# all.net
KiCad netlist of a schematic drawn in Altium Designer
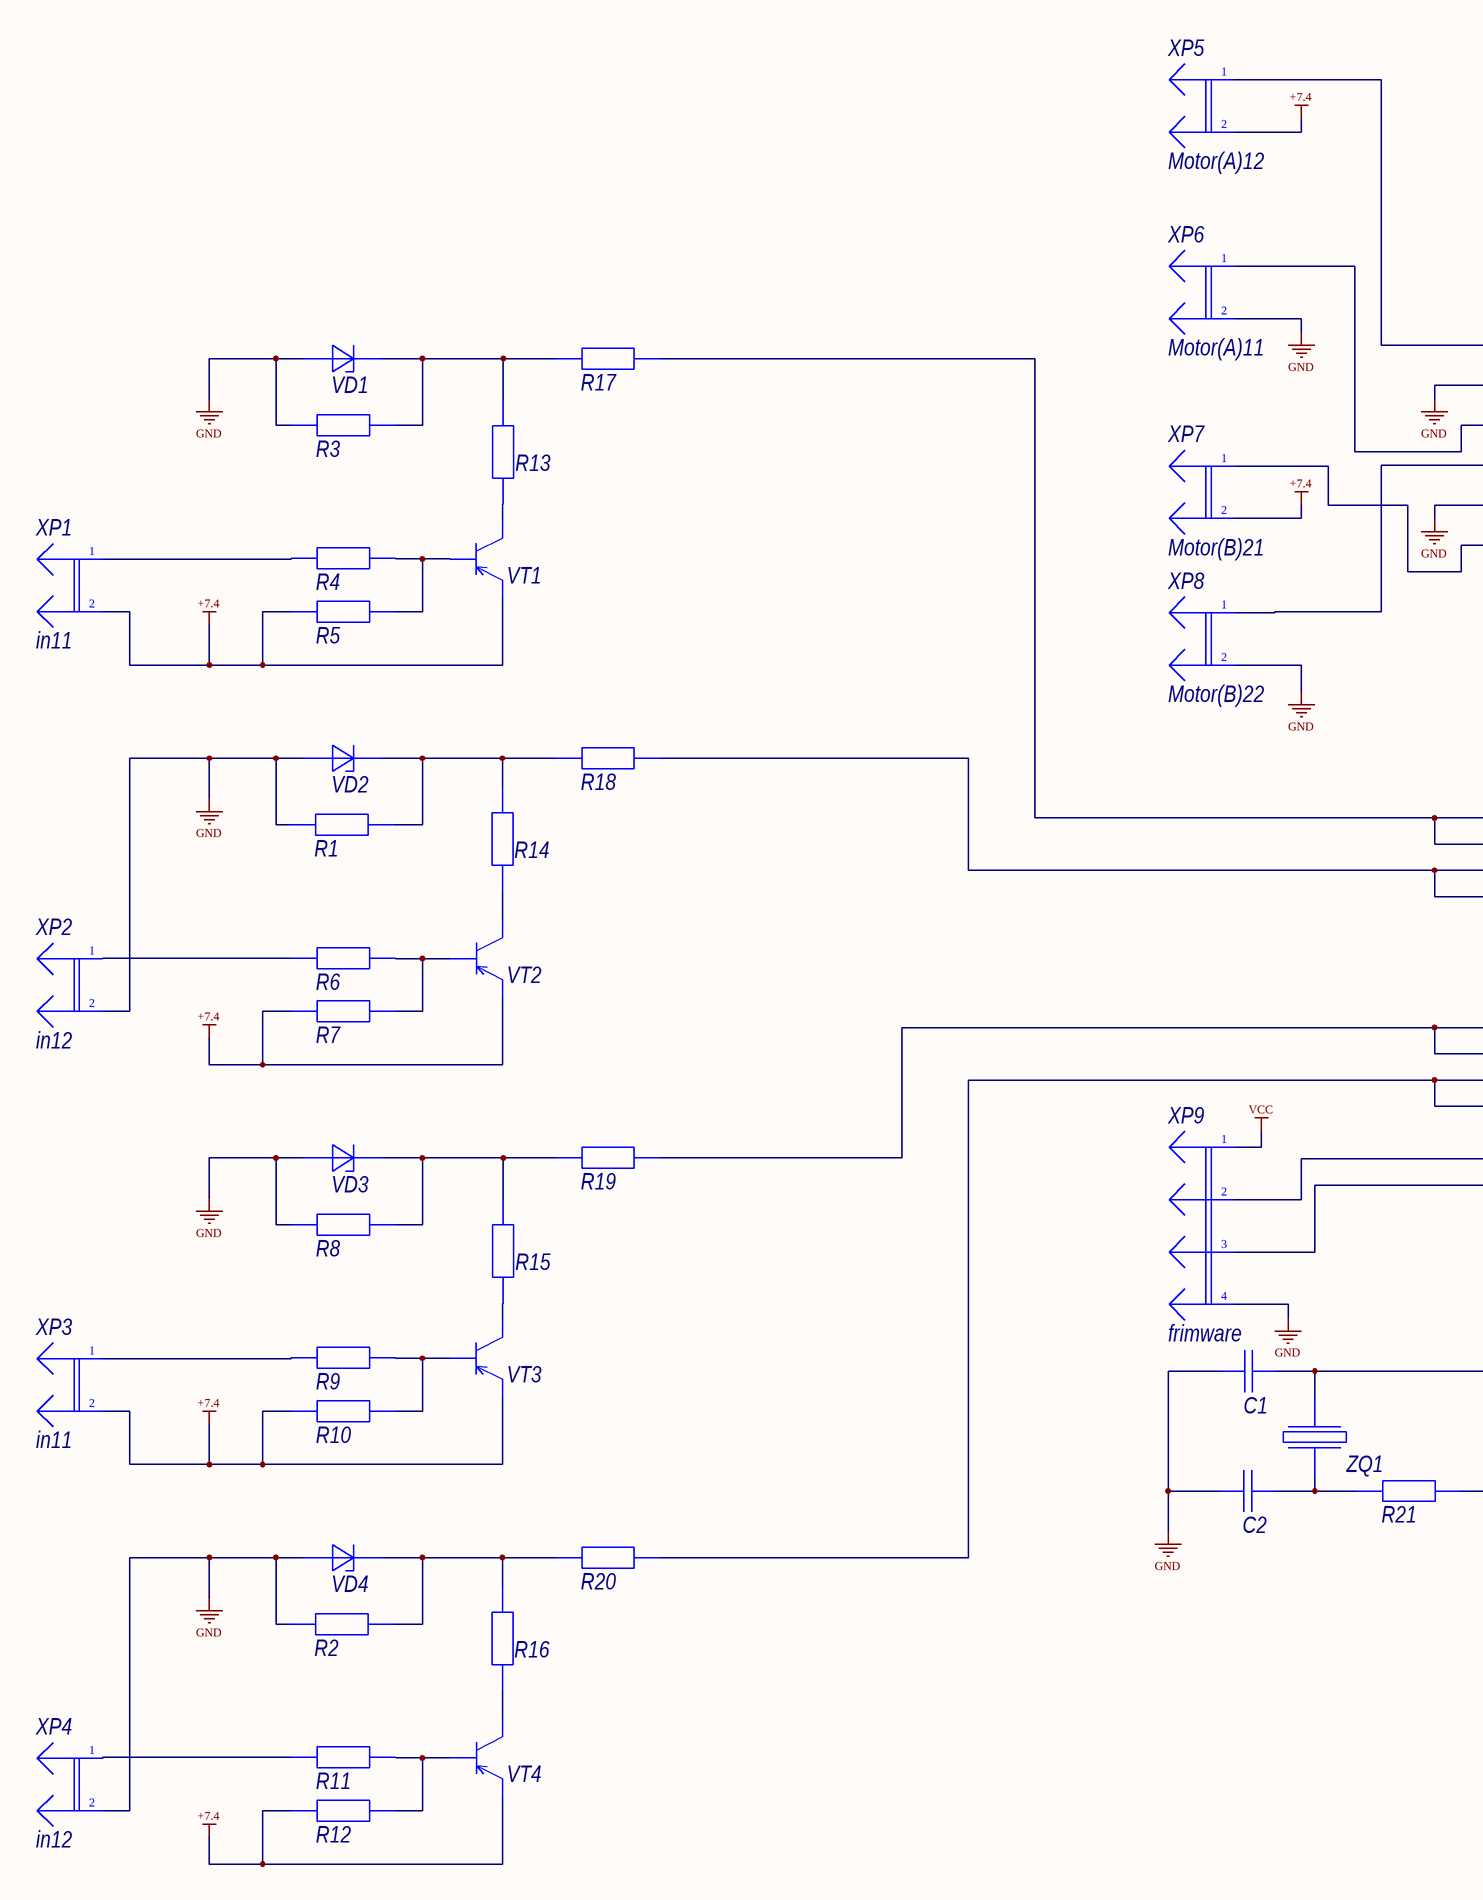
[diagram p0: all.SchDoc, left]
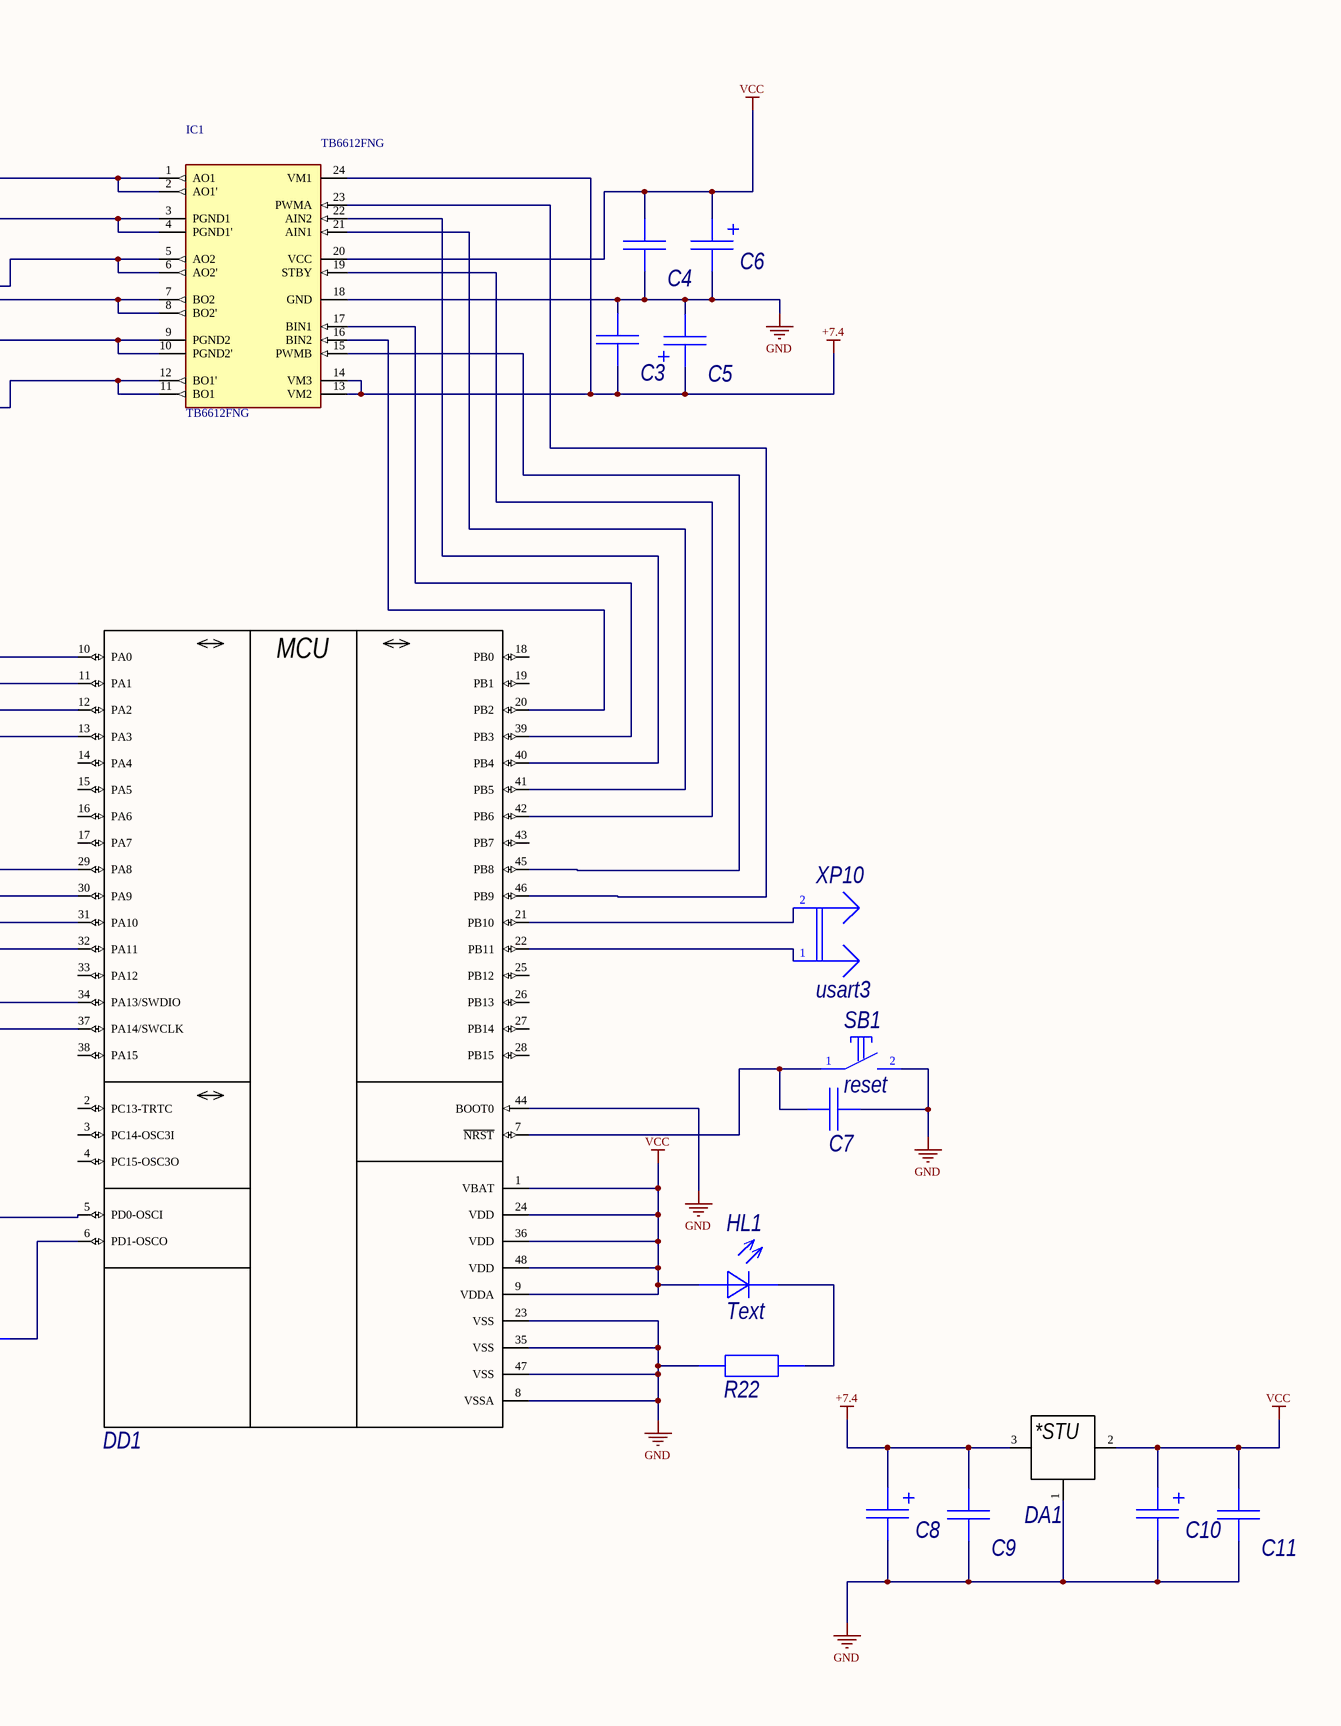
[diagram p1: all.SchDoc, right]

(export (version "E")
  (design (tool "Eeschema 10.0.6"))
  (components
    (comp (ref "C1")
      (value "Capacitor")
      (footprint "C0603")
      (description "30pF 0603")
      (fields
        (field (name "PART NUMBER") "GRM1885C1H300FA01D")
        (field (name "VOLTAGE") "50V")
        (field (name "PUBLISHER") "Andrew Danich")
      )
      (libsource (lib "Lib_IMP_GOST") (part "Capacitor"))
    )
    (comp (ref "C2")
      (value "Capacitor")
      (footprint "C0603")
      (description "30pF 0603")
      (fields
        (field (name "PART NUMBER") "GRM1885C1H300FA01D")
        (field (name "VOLTAGE") "50V")
        (field (name "PUBLISHER") "Andrew Danich")
      )
      (libsource (lib "Lib_IMP_GOST") (part "Capacitor"))
    )
    (comp (ref "C3")
      (value "Capacitor")
      (footprint "C0603")
      (description "0.1 uF")
      (fields
        (field (name "PART NUMBER") "GRM188R71C104KA01D")
        (field (name "VOLTAGE") "16V")
        (field (name "PUBLISHER") "Andrew Danich")
      )
      (libsource (lib "Lib_IMP_GOST") (part "Capacitor"))
    )
    (comp (ref "C4")
      (value "Capacitor")
      (footprint "C0603")
      (description "0.1 uF")
      (fields
        (field (name "PART NUMBER") "GRM188R71C104KA01D")
        (field (name "VOLTAGE") "16V")
        (field (name "PUBLISHER") "Andrew Danich")
      )
      (libsource (lib "Lib_IMP_GOST") (part "Capacitor"))
    )
    (comp (ref "C5")
      (value "Capacitor-T")
      (footprint "C3216-p")
      (description "10 uF")
      (fields
        (field (name "PART NUMBER") "T491A106K006AT")
        (field (name "VOLTAGE") "6.3V")
        (field (name "PUBLISHER") "Andrew Danich")
      )
      (libsource (lib "Lib_IMP_GOST") (part "Capacitor-T"))
    )
    (comp (ref "C6")
      (value "Capacitor-T")
      (footprint "C3216-p")
      (description "10 uF")
      (fields
        (field (name "PART NUMBER") "T491A106K006AT")
        (field (name "VOLTAGE") "6.3V")
        (field (name "PUBLISHER") "Andrew Danich")
      )
      (libsource (lib "Lib_IMP_GOST") (part "Capacitor-T"))
    )
    (comp (ref "C7")
      (value "Capacitor")
      (footprint "C0603")
      (description "0.1 uF 0603")
      (fields
        (field (name "PART NUMBER") "GRM188R71C104KA01D")
        (field (name "VOLTAGE") "16V")
        (field (name "PUBLISHER") "Andrew Danich")
      )
      (libsource (lib "Lib_IMP_GOST") (part "Capacitor"))
    )
    (comp (ref "C8")
      (value "Capacitor-T")
      (footprint "C3216-p")
      (description "10 uF")
      (fields
        (field (name "PART NUMBER") "T491A106K006AT")
        (field (name "VOLTAGE") "6.3V")
        (field (name "PUBLISHER") "Andrew Danich")
      )
      (libsource (lib "Lib_IMP_GOST") (part "Capacitor-T"))
    )
    (comp (ref "C9")
      (value "Capacitor")
      (footprint "C0603")
      (description "0.1 uF")
      (fields
        (field (name "PART NUMBER") "GRM188R71C104KA01D")
        (field (name "VOLTAGE") "16V")
        (field (name "PUBLISHER") "Andrew Danich")
      )
      (libsource (lib "Lib_IMP_GOST") (part "Capacitor"))
    )
    (comp (ref "C10")
      (value "Capacitor-T")
      (footprint "C3216-p")
      (description "10 uF")
      (fields
        (field (name "PART NUMBER") "T491A106K006AT")
        (field (name "VOLTAGE") "6.3V")
        (field (name "PUBLISHER") "Andrew Danich")
      )
      (libsource (lib "Lib_IMP_GOST") (part "Capacitor-T"))
    )
    (comp (ref "C11")
      (value "Capacitor")
      (footprint "C0603")
      (description "0.1 uF")
      (fields
        (field (name "PART NUMBER") "GRM188R71C104KA01D")
        (field (name "VOLTAGE") "16V")
        (field (name "PUBLISHER") "Andrew Danich")
      )
      (libsource (lib "Lib_IMP_GOST") (part "Capacitor"))
    )
    (comp (ref "DA1")
      (value "LM1117-Series")
      (footprint "SOT-223")
      (fields (field (name "PART NUMBER") "LM1117MPX-ADJ") (field (name "PUBLISHER") "Andrew Danich"))
      (libsource (lib "Lib_IMP_GOST") (part "LM1117-Series"))
    )
    (comp (ref "DD1")
      (value "STM32F103Cxxx-Series")
      (footprint "LQFP-48")
      (fields
        (field (name "PART NUMBER") "STM32F103C8T6")
        (field (name "MANUFACTURER") "STMicroelectronics")
        (field (name "PUBLISHER") "Andrew Danich")
      )
      (libsource (lib "Lib_IMP_GOST") (part "STM32F103Cxxx-Series"))
    )
    (comp (ref "HL1")
      (value "Text")
      (footprint "LD0805")
      (fields
        (field (name "PART NUMBER") "KP-2012SGC")
        (field (name "MANUFACTURER") "Kingbright")
        (field (name "PUBLISHER") "Andrew Danich")
      )
      (libsource (lib "Lib_IMP_GOST") (part "Led-1"))
    )
    (comp (ref "IC1")
      (value "TB6612FNG")
      (footprint "SSOP24")
      (description "Motor Driver Power MOSFET Parallel 24-SSOP")
      (fields (field (name "MF") "Toshiba"))
      (libsource (lib "TB6612FNG") (part "TB6612FNG"))
    )
    (comp (ref "R1")
      (value "Resistor")
      (footprint "R0402")
      (description "10k")
      (fields
        (field (name "PART NUMBER") "RC0402FR-07100KL")
        (field (name "TOLERANCE") "±1%")
        (field (name "PUBLISHER") "Andrew Danich")
      )
      (libsource (lib "Lib_IMP_GOST") (part "Resistor"))
    )
    (comp (ref "R2")
      (value "Resistor")
      (footprint "R0402")
      (description "10k")
      (fields
        (field (name "PART NUMBER") "RC0402FR-07100KL")
        (field (name "TOLERANCE") "±1%")
        (field (name "PUBLISHER") "Andrew Danich")
      )
      (libsource (lib "Lib_IMP_GOST") (part "Resistor"))
    )
    (comp (ref "R3")
      (value "Resistor")
      (footprint "R0603")
      (description "10K")
      (fields
        (field (name "PART NUMBER") "RC0603JR-0710KL")
        (field (name "TOLERANCE") "±5%")
        (field (name "PUBLISHER") "Andrew Danich")
      )
      (libsource (lib "Lib_IMP_GOST") (part "Resistor"))
    )
    (comp (ref "R4")
      (value "Resistor")
      (footprint "R0603")
      (description "10K")
      (fields
        (field (name "PART NUMBER") "RC0603JR-0710KL")
        (field (name "TOLERANCE") "±5%")
        (field (name "PUBLISHER") "Andrew Danich")
      )
      (libsource (lib "Lib_IMP_GOST") (part "Resistor"))
    )
    (comp (ref "R5")
      (value "Resistor")
      (footprint "R0603")
      (description "100k")
      (fields
        (field (name "PART NUMBER") "RC0603JR-07100KL")
        (field (name "TOLERANCE") "±5%")
        (field (name "PUBLISHER") "Andrew Danich")
      )
      (libsource (lib "Lib_IMP_GOST") (part "Resistor"))
    )
    (comp (ref "R6")
      (value "Resistor")
      (footprint "R0603")
      (description "10K")
      (fields
        (field (name "PART NUMBER") "RC0603JR-0710KL")
        (field (name "TOLERANCE") "±5%")
        (field (name "PUBLISHER") "Andrew Danich")
      )
      (libsource (lib "Lib_IMP_GOST") (part "Resistor"))
    )
    (comp (ref "R7")
      (value "Resistor")
      (footprint "R0603")
      (description "10K")
      (fields
        (field (name "PART NUMBER") "RC0603JR-0710KL")
        (field (name "TOLERANCE") "±5%")
        (field (name "PUBLISHER") "Andrew Danich")
      )
      (libsource (lib "Lib_IMP_GOST") (part "Resistor"))
    )
    (comp (ref "R8")
      (value "Resistor")
      (footprint "R0603")
      (description "10K")
      (fields
        (field (name "PART NUMBER") "RC0603JR-0710KL")
        (field (name "TOLERANCE") "±5%")
        (field (name "PUBLISHER") "Andrew Danich")
      )
      (libsource (lib "Lib_IMP_GOST") (part "Resistor"))
    )
    (comp (ref "R9")
      (value "Resistor")
      (footprint "R0603")
      (description "10K")
      (fields
        (field (name "PART NUMBER") "RC0603JR-0710KL")
        (field (name "TOLERANCE") "±5%")
        (field (name "PUBLISHER") "Andrew Danich")
      )
      (libsource (lib "Lib_IMP_GOST") (part "Resistor"))
    )
    (comp (ref "R10")
      (value "Resistor")
      (footprint "R0603")
      (description "100k")
      (fields
        (field (name "PART NUMBER") "RC0603JR-07100KL")
        (field (name "TOLERANCE") "±5%")
        (field (name "PUBLISHER") "Andrew Danich")
      )
      (libsource (lib "Lib_IMP_GOST") (part "Resistor"))
    )
    (comp (ref "R11")
      (value "Resistor")
      (footprint "R0603")
      (description "10K")
      (fields
        (field (name "PART NUMBER") "RC0603JR-0710KL")
        (field (name "TOLERANCE") "±5%")
        (field (name "PUBLISHER") "Andrew Danich")
      )
      (libsource (lib "Lib_IMP_GOST") (part "Resistor"))
    )
    (comp (ref "R12")
      (value "Resistor")
      (footprint "R0603")
      (description "10K")
      (fields
        (field (name "PART NUMBER") "RC0603JR-0710KL")
        (field (name "TOLERANCE") "±5%")
        (field (name "PUBLISHER") "Andrew Danich")
      )
      (libsource (lib "Lib_IMP_GOST") (part "Resistor"))
    )
    (comp (ref "R13")
      (value "Resistor")
      (footprint "R0603")
      (description "1k")
      (fields
        (field (name "PART NUMBER") "RC0603JR-071KL")
        (field (name "TOLERANCE") "±5%")
        (field (name "PUBLISHER") "Andrew Danich")
      )
      (libsource (lib "Lib_IMP_GOST") (part "Resistor"))
    )
    (comp (ref "R14")
      (value "Resistor")
      (footprint "R0603")
      (description "1k")
      (fields
        (field (name "PART NUMBER") "RC0603JR-071KL")
        (field (name "TOLERANCE") "±5%")
        (field (name "PUBLISHER") "Andrew Danich")
      )
      (libsource (lib "Lib_IMP_GOST") (part "Resistor"))
    )
    (comp (ref "R15")
      (value "Resistor")
      (footprint "R0603")
      (description "1k")
      (fields
        (field (name "PART NUMBER") "RC0603JR-071KL")
        (field (name "TOLERANCE") "±5%")
        (field (name "PUBLISHER") "Andrew Danich")
      )
      (libsource (lib "Lib_IMP_GOST") (part "Resistor"))
    )
    (comp (ref "R16")
      (value "Resistor")
      (footprint "R0603")
      (description "1k")
      (fields
        (field (name "PART NUMBER") "RC0603JR-071KL")
        (field (name "TOLERANCE") "±5%")
        (field (name "PUBLISHER") "Andrew Danich")
      )
      (libsource (lib "Lib_IMP_GOST") (part "Resistor"))
    )
    (comp (ref "R17")
      (value "Resistor")
      (footprint "R0603")
      (description "1k")
      (fields
        (field (name "PART NUMBER") "RC0603JR-071KL")
        (field (name "TOLERANCE") "±5%")
        (field (name "PUBLISHER") "Andrew Danich")
      )
      (libsource (lib "Lib_IMP_GOST") (part "Resistor"))
    )
    (comp (ref "R18")
      (value "Resistor")
      (footprint "R0603")
      (description "1k")
      (fields
        (field (name "PART NUMBER") "RC0603JR-071KL")
        (field (name "TOLERANCE") "±5%")
        (field (name "PUBLISHER") "Andrew Danich")
      )
      (libsource (lib "Lib_IMP_GOST") (part "Resistor"))
    )
    (comp (ref "R19")
      (value "Resistor")
      (footprint "R0603")
      (description "1k")
      (fields
        (field (name "PART NUMBER") "RC0603JR-071KL")
        (field (name "TOLERANCE") "±5%")
        (field (name "PUBLISHER") "Andrew Danich")
      )
      (libsource (lib "Lib_IMP_GOST") (part "Resistor"))
    )
    (comp (ref "R20")
      (value "Resistor")
      (footprint "R0603")
      (description "1k")
      (fields
        (field (name "PART NUMBER") "RC0603JR-071KL")
        (field (name "TOLERANCE") "±5%")
        (field (name "PUBLISHER") "Andrew Danich")
      )
      (libsource (lib "Lib_IMP_GOST") (part "Resistor"))
    )
    (comp (ref "R21")
      (value "Resistor")
      (footprint "R0603")
      (description "200 kOm")
      (fields
        (field (name "PART NUMBER") "RC0603FR-07200KL")
        (field (name "TOLERANCE") "±1%")
        (field (name "PUBLISHER") "Andrew Danich")
      )
      (libsource (lib "Lib_IMP_GOST") (part "Resistor"))
    )
    (comp (ref "R22")
      (value "Resistor")
      (footprint "R0805")
      (fields
        (field (name "PART NUMBER") "RC0805JR-0768RL")
        (field (name "TOLERANCE") "±5%")
        (field (name "MANUFACTURER") "Yageo")
        (field (name "PUBLISHER") "Andrew Danich")
      )
      (libsource (lib "Lib_IMP_GOST") (part "Resistor"))
    )
    (comp (ref "SB1")
      (value "reset")
      (footprint "DTS-32")
      (fields (field (name "PART NUMBER") "DTS-32") (field (name "PUBLISHER") "Andrew Danich"))
      (libsource (lib "Lib_IMP_GOST") (part "BT-01x-01p"))
    )
    (comp (ref "VD1")
      (value "Zener")
      (footprint "SOT-23")
      (fields
        (field (name "PART NUMBER") "BZX84-C3V3")
        (field (name "MANUFACTURER") "NXP")
        (field (name "PUBLISHER") "Andrew Danich")
      )
      (libsource (lib "Lib_IMP_GOST") (part "Zener"))
    )
    (comp (ref "VD2")
      (value "Zener")
      (footprint "SOT-23")
      (fields
        (field (name "PART NUMBER") "BZX84-C3V3")
        (field (name "MANUFACTURER") "NXP")
        (field (name "PUBLISHER") "Andrew Danich")
      )
      (libsource (lib "Lib_IMP_GOST") (part "Zener"))
    )
    (comp (ref "VD3")
      (value "Zener")
      (footprint "SOT-23")
      (fields
        (field (name "PART NUMBER") "BZX84-C3V3")
        (field (name "MANUFACTURER") "NXP")
        (field (name "PUBLISHER") "Andrew Danich")
      )
      (libsource (lib "Lib_IMP_GOST") (part "Zener"))
    )
    (comp (ref "VD4")
      (value "Zener")
      (footprint "SOT-23")
      (fields
        (field (name "PART NUMBER") "BZX84-C3V3")
        (field (name "MANUFACTURER") "NXP")
        (field (name "PUBLISHER") "Andrew Danich")
      )
      (libsource (lib "Lib_IMP_GOST") (part "Zener"))
    )
    (comp (ref "VT1")
      (value "BJT-PNP")
      (footprint "SOT-23")
      (fields (field (name "PART NUMBER") "BC857") (field (name "PUBLISHER") "Andrew Danich"))
      (libsource (lib "Lib_IMP_GOST") (part "BJT-PNP"))
    )
    (comp (ref "VT2")
      (value "BJT-PNP")
      (footprint "SOT-23")
      (fields (field (name "PART NUMBER") "BC857") (field (name "PUBLISHER") "Andrew Danich"))
      (libsource (lib "Lib_IMP_GOST") (part "BJT-PNP"))
    )
    (comp (ref "VT3")
      (value "BJT-PNP")
      (footprint "SOT-23")
      (fields (field (name "PART NUMBER") "BC857") (field (name "PUBLISHER") "Andrew Danich"))
      (libsource (lib "Lib_IMP_GOST") (part "BJT-PNP"))
    )
    (comp (ref "VT4")
      (value "BJT-PNP")
      (footprint "SOT-23")
      (fields (field (name "PART NUMBER") "BC857") (field (name "PUBLISHER") "Andrew Danich"))
      (libsource (lib "Lib_IMP_GOST") (part "BJT-PNP"))
    )
    (comp (ref "XP1")
      (value "in11")
      (footprint "PLS-2")
      (fields (field (name "PART NUMBER") "PLS-2") (field (name "PUBLISHER") "Andrew Danich"))
      (libsource (lib "Lib_IMP_GOST") (part "Con-2-M"))
    )
    (comp (ref "XP2")
      (value "in12")
      (footprint "PLS-2")
      (fields (field (name "PART NUMBER") "PLS-2") (field (name "PUBLISHER") "Andrew Danich"))
      (libsource (lib "Lib_IMP_GOST") (part "Con-2-M"))
    )
    (comp (ref "XP3")
      (value "in11")
      (footprint "PLS-2")
      (fields (field (name "PART NUMBER") "PLS-2") (field (name "PUBLISHER") "Andrew Danich"))
      (libsource (lib "Lib_IMP_GOST") (part "Con-2-M"))
    )
    (comp (ref "XP4")
      (value "in12")
      (footprint "PLS-2")
      (fields (field (name "PART NUMBER") "PLS-2") (field (name "PUBLISHER") "Andrew Danich"))
      (libsource (lib "Lib_IMP_GOST") (part "Con-2-M"))
    )
    (comp (ref "XP5")
      (value "Motor(A)12")
      (footprint "PLS-2")
      (fields (field (name "PART NUMBER") "PLS-2") (field (name "PUBLISHER") "Andrew Danich"))
      (libsource (lib "Lib_IMP_GOST") (part "Con-2-M"))
    )
    (comp (ref "XP6")
      (value "Motor(A)11")
      (footprint "PLS-2")
      (fields (field (name "PART NUMBER") "PLS-2") (field (name "PUBLISHER") "Andrew Danich"))
      (libsource (lib "Lib_IMP_GOST") (part "Con-2-M"))
    )
    (comp (ref "XP7")
      (value "Motor(B)21")
      (footprint "PLS-2")
      (fields (field (name "PART NUMBER") "PLS-2") (field (name "PUBLISHER") "Andrew Danich"))
      (libsource (lib "Lib_IMP_GOST") (part "Con-2-M"))
    )
    (comp (ref "XP8")
      (value "Motor(B)22")
      (footprint "PLS-2")
      (fields (field (name "PART NUMBER") "PLS-2") (field (name "PUBLISHER") "Andrew Danich"))
      (libsource (lib "Lib_IMP_GOST") (part "Con-2-M"))
    )
    (comp (ref "XP9")
      (value "frimware")
      (footprint "PLS-4RR")
      (fields (field (name "PART NUMBER") "PLS-4R") (field (name "PUBLISHER") "Andrew Danich"))
      (libsource (lib "Lib_IMP_GOST") (part "Con-4-M"))
    )
    (comp (ref "XP10")
      (value "usart3")
      (footprint "PLS-2RR")
      (fields (field (name "PART NUMBER") "PLS-2R") (field (name "PUBLISHER") "Andrew Danich"))
      (libsource (lib "Lib_IMP_GOST") (part "Con-2-M"))
    )
    (comp (ref "ZQ1")
      (value "Crystal")
      (footprint "HC-49S")
      (description "8MHz")
      (fields (field (name "PART NUMBER") "HC-49S 8MHz") (field (name "PUBLISHER") "Andrew Danich"))
      (libsource (lib "Lib_IMP_GOST") (part "Crystal"))
    )
  )
  (nets
    (net (code "1") (name "+7.4") (class "Default")
      (node (ref "C3") (pin "1") (pinfunction "1_1") (pintype "passive"))
      (node (ref "C5") (pin "1") (pinfunction "1_1") (pintype "passive"))
      (node (ref "C8") (pin "1") (pinfunction "1_1") (pintype "passive"))
      (node (ref "C9") (pin "1") (pinfunction "1_1") (pintype "passive"))
      (node (ref "DA1") (pin "3") (pinfunction "In_3") (pintype "passive"))
      (node (ref "IC1") (pin "13") (pinfunction "VM2_13") (pintype "power_in"))
      (node (ref "IC1") (pin "14") (pinfunction "VM3_14") (pintype "power_in"))
      (node (ref "IC1") (pin "24") (pinfunction "VM1_24") (pintype "power_in"))
      (node (ref "R10") (pin "1") (pinfunction "1_1") (pintype "passive"))
      (node (ref "R12") (pin "1") (pinfunction "1_1") (pintype "passive"))
      (node (ref "R5") (pin "1") (pinfunction "1_1") (pintype "passive"))
      (node (ref "R7") (pin "1") (pinfunction "1_1") (pintype "passive"))
      (node (ref "VT1") (pin "3") (pinfunction "Э_3") (pintype "passive"))
      (node (ref "VT2") (pin "3") (pinfunction "Э_3") (pintype "passive"))
      (node (ref "VT3") (pin "3") (pinfunction "Э_3") (pintype "passive"))
      (node (ref "VT4") (pin "3") (pinfunction "Э_3") (pintype "passive"))
      (node (ref "XP1") (pin "2") (pintype "passive"))
      (node (ref "XP3") (pin "2") (pintype "passive"))
      (node (ref "XP5") (pin "2") (pintype "passive"))
      (node (ref "XP7") (pin "2") (pintype "passive"))
    )
    (net (code "2") (name "GND") (class "Default")
      (node (ref "C1") (pin "1") (pinfunction "1_1") (pintype "passive"))
      (node (ref "C10") (pin "2") (pinfunction "2_2") (pintype "passive"))
      (node (ref "C11") (pin "2") (pinfunction "2_2") (pintype "passive"))
      (node (ref "C2") (pin "1") (pinfunction "1_1") (pintype "passive"))
      (node (ref "C3") (pin "2") (pinfunction "2_2") (pintype "passive"))
      (node (ref "C4") (pin "1") (pinfunction "1_1") (pintype "passive"))
      (node (ref "C5") (pin "2") (pinfunction "2_2") (pintype "passive"))
      (node (ref "C6") (pin "2") (pinfunction "2_2") (pintype "passive"))
      (node (ref "C7") (pin "2") (pinfunction "2_2") (pintype "passive"))
      (node (ref "C8") (pin "2") (pinfunction "2_2") (pintype "passive"))
      (node (ref "C9") (pin "2") (pinfunction "2_2") (pintype "passive"))
      (node (ref "DA1") (pin "1") (pinfunction "Adj/GND_1") (pintype "passive"))
      (node (ref "DD1") (pin "23") (pinfunction "VSS_23") (pintype "power_in"))
      (node (ref "DD1") (pin "35") (pinfunction "VSS_35") (pintype "power_in"))
      (node (ref "DD1") (pin "44") (pinfunction "BOOT0_44") (pintype "input"))
      (node (ref "DD1") (pin "47") (pinfunction "VSS_47") (pintype "power_in"))
      (node (ref "DD1") (pin "8") (pinfunction "VSSA_8") (pintype "power_in"))
      (node (ref "IC1") (pin "10") (pinfunction "PGND2'_10") (pintype "power_in"))
      (node (ref "IC1") (pin "18") (pinfunction "GND_18") (pintype "power_in"))
      (node (ref "IC1") (pin "3") (pinfunction "PGND1_3") (pintype "power_in"))
      (node (ref "IC1") (pin "4") (pinfunction "PGND1'_4") (pintype "power_in"))
      (node (ref "IC1") (pin "9") (pinfunction "PGND2_9") (pintype "power_in"))
      (node (ref "R1") (pin "2") (pinfunction "2_2") (pintype "passive"))
      (node (ref "R2") (pin "2") (pinfunction "2_2") (pintype "passive"))
      (node (ref "R22") (pin "1") (pinfunction "1_1") (pintype "passive"))
      (node (ref "R3") (pin "1") (pinfunction "1_1") (pintype "passive"))
      (node (ref "R8") (pin "1") (pinfunction "1_1") (pintype "passive"))
      (node (ref "SB1") (pin "2") (pintype "passive"))
      (node (ref "VD1") (pin "1") (pinfunction "А_1") (pintype "passive"))
      (node (ref "VD2") (pin "1") (pinfunction "А_1") (pintype "passive"))
      (node (ref "VD3") (pin "1") (pinfunction "А_1") (pintype "passive"))
      (node (ref "VD4") (pin "1") (pinfunction "А_1") (pintype "passive"))
      (node (ref "XP2") (pin "2") (pintype "passive"))
      (node (ref "XP4") (pin "2") (pintype "passive"))
      (node (ref "XP6") (pin "2") (pintype "passive"))
      (node (ref "XP8") (pin "2") (pintype "passive"))
      (node (ref "XP9") (pin "4") (pintype "passive"))
    )
    (net (code "3") (name "Net-(C2-Pad2)") (class "Default")
      (node (ref "C2") (pin "2") (pinfunction "2_2") (pintype "passive"))
      (node (ref "R21") (pin "1") (pinfunction "1_1") (pintype "passive"))
      (node (ref "ZQ1") (pin "1") (pinfunction "1_1") (pintype "passive"))
    )
    (net (code "4") (name "Net-(DD1-PA0)") (class "Default")
      (node (ref "DD1") (pin "10") (pinfunction "PA0_10") (pintype "bidirectional"))
      (node (ref "DD1") (pin "11") (pinfunction "PA1_11") (pintype "bidirectional"))
      (node (ref "R17") (pin "1") (pinfunction "1_1") (pintype "passive"))
    )
    (net (code "5") (name "Net-(DD1-PA2)") (class "Default")
      (node (ref "DD1") (pin "12") (pinfunction "PA2_12") (pintype "bidirectional"))
      (node (ref "DD1") (pin "13") (pinfunction "PA3_13") (pintype "bidirectional"))
      (node (ref "R18") (pin "1") (pinfunction "1_1") (pintype "passive"))
    )
    (net (code "6") (name "Net-(DD1-PA8)") (class "Default")
      (node (ref "DD1") (pin "29") (pinfunction "PA8_29") (pintype "bidirectional"))
      (node (ref "DD1") (pin "30") (pinfunction "PA9_30") (pintype "bidirectional"))
      (node (ref "R19") (pin "1") (pinfunction "1_1") (pintype "passive"))
    )
    (net (code "7") (name "Net-(DD1-PA10)") (class "Default")
      (node (ref "DD1") (pin "31") (pinfunction "PA10_31") (pintype "bidirectional"))
      (node (ref "DD1") (pin "32") (pinfunction "PA11_32") (pintype "bidirectional"))
      (node (ref "R20") (pin "1") (pinfunction "1_1") (pintype "passive"))
    )
    (net (code "8") (name "Net-(DD1-PA13{slash}SWDIO)") (class "Default")
      (node (ref "DD1") (pin "34") (pinfunction "PA13/SWDIO_34") (pintype "bidirectional"))
      (node (ref "XP9") (pin "2") (pintype "passive"))
    )
    (net (code "9") (name "Net-(DD1-PA14{slash}SWCLK)") (class "Default")
      (node (ref "DD1") (pin "37") (pinfunction "PA14/SWCLK_37") (pintype "bidirectional"))
      (node (ref "XP9") (pin "3") (pintype "passive"))
    )
    (net (code "10") (name "Net-(DD1-PB2)") (class "Default")
      (node (ref "DD1") (pin "20") (pinfunction "PB2_20") (pintype "bidirectional"))
      (node (ref "IC1") (pin "16") (pinfunction "BIN2_16") (pintype "input"))
    )
    (net (code "11") (name "Net-(DD1-PB3)") (class "Default")
      (node (ref "DD1") (pin "39") (pinfunction "PB3_39") (pintype "bidirectional"))
      (node (ref "IC1") (pin "17") (pinfunction "BIN1_17") (pintype "input"))
    )
    (net (code "12") (name "Net-(DD1-PB4)") (class "Default")
      (node (ref "DD1") (pin "40") (pinfunction "PB4_40") (pintype "bidirectional"))
      (node (ref "IC1") (pin "22") (pinfunction "AIN2_22") (pintype "input"))
    )
    (net (code "13") (name "Net-(DD1-PB5)") (class "Default")
      (node (ref "DD1") (pin "41") (pinfunction "PB5_41") (pintype "bidirectional"))
      (node (ref "IC1") (pin "21") (pinfunction "AIN1_21") (pintype "input"))
    )
    (net (code "14") (name "Net-(DD1-PB6)") (class "Default")
      (node (ref "DD1") (pin "42") (pinfunction "PB6_42") (pintype "bidirectional"))
      (node (ref "IC1") (pin "19") (pinfunction "STBY_19") (pintype "input"))
    )
    (net (code "15") (name "Net-(DD1-PB8)") (class "Default")
      (node (ref "DD1") (pin "45") (pinfunction "PB8_45") (pintype "bidirectional"))
      (node (ref "IC1") (pin "15") (pinfunction "PWMB_15") (pintype "input"))
    )
    (net (code "16") (name "Net-(DD1-PB9)") (class "Default")
      (node (ref "DD1") (pin "46") (pinfunction "PB9_46") (pintype "bidirectional"))
      (node (ref "IC1") (pin "23") (pinfunction "PWMA_23") (pintype "input"))
    )
    (net (code "17") (name "Net-(DD1-PB10)") (class "Default")
      (node (ref "DD1") (pin "21") (pinfunction "PB10_21") (pintype "bidirectional"))
      (node (ref "XP10") (pin "2") (pintype "passive"))
    )
    (net (code "18") (name "Net-(DD1-PB11)") (class "Default")
      (node (ref "DD1") (pin "22") (pinfunction "PB11_22") (pintype "bidirectional"))
      (node (ref "XP10") (pin "1") (pintype "passive"))
    )
    (net (code "19") (name "Net-(DD1-PD0-OSCI)") (class "Default")
      (node (ref "C1") (pin "2") (pinfunction "2_2") (pintype "passive"))
      (node (ref "DD1") (pin "5") (pinfunction "PD0-OSCI_5") (pintype "bidirectional"))
      (node (ref "ZQ1") (pin "3") (pinfunction "3_3") (pintype "passive"))
    )
    (net (code "20") (name "Net-(DD1-PD1-OSCO)") (class "Default")
      (node (ref "DD1") (pin "6") (pinfunction "PD1-OSCO_6") (pintype "bidirectional"))
      (node (ref "R21") (pin "2") (pinfunction "2_2") (pintype "passive"))
    )
    (net (code "21") (name "Net-(DD1-~{NRST})") (class "Default")
      (node (ref "C7") (pin "1") (pinfunction "1_1") (pintype "passive"))
      (node (ref "DD1") (pin "7") (pinfunction "~{NRST}_7") (pintype "bidirectional"))
      (node (ref "SB1") (pin "1") (pintype "passive"))
    )
    (net (code "22") (name "Net-(HL1-К)") (class "Default")
      (node (ref "HL1") (pin "2") (pinfunction "К_2") (pintype "passive"))
      (node (ref "R22") (pin "2") (pinfunction "2_2") (pintype "passive"))
    )
    (net (code "23") (name "Net-(IC1-AO1')") (class "Default")
      (node (ref "IC1") (pin "1") (pinfunction "AO1_1") (pintype "output"))
      (node (ref "IC1") (pin "2") (pinfunction "AO1'_2") (pintype "output"))
      (node (ref "XP5") (pin "1") (pintype "passive"))
    )
    (net (code "24") (name "Net-(IC1-AO2')") (class "Default")
      (node (ref "IC1") (pin "5") (pinfunction "AO2_5") (pintype "output"))
      (node (ref "IC1") (pin "6") (pinfunction "AO2'_6") (pintype "output"))
      (node (ref "XP6") (pin "1") (pintype "passive"))
    )
    (net (code "25") (name "Net-(IC1-BO1')") (class "Default")
      (node (ref "IC1") (pin "11") (pinfunction "BO1_11") (pintype "output"))
      (node (ref "IC1") (pin "12") (pinfunction "BO1'_12") (pintype "output"))
      (node (ref "XP7") (pin "1") (pintype "passive"))
    )
    (net (code "26") (name "Net-(IC1-BO2')") (class "Default")
      (node (ref "IC1") (pin "7") (pinfunction "BO2_7") (pintype "output"))
      (node (ref "IC1") (pin "8") (pinfunction "BO2'_8") (pintype "output"))
      (node (ref "XP8") (pin "1") (pintype "passive"))
    )
    (net (code "27") (name "Net-(R4-Pad1)") (class "Default")
      (node (ref "R4") (pin "1") (pinfunction "1_1") (pintype "passive"))
      (node (ref "XP1") (pin "1") (pintype "passive"))
    )
    (net (code "28") (name "Net-(R6-Pad1)") (class "Default")
      (node (ref "R6") (pin "1") (pinfunction "1_1") (pintype "passive"))
      (node (ref "XP2") (pin "1") (pintype "passive"))
    )
    (net (code "29") (name "Net-(R9-Pad1)") (class "Default")
      (node (ref "R9") (pin "1") (pinfunction "1_1") (pintype "passive"))
      (node (ref "XP3") (pin "1") (pintype "passive"))
    )
    (net (code "30") (name "Net-(R11-Pad1)") (class "Default")
      (node (ref "R11") (pin "1") (pinfunction "1_1") (pintype "passive"))
      (node (ref "XP4") (pin "1") (pintype "passive"))
    )
    (net (code "31") (name "Net-(VD1-К)") (class "Default")
      (node (ref "R13") (pin "1") (pinfunction "1_1") (pintype "passive"))
      (node (ref "R17") (pin "2") (pinfunction "2_2") (pintype "passive"))
      (node (ref "R3") (pin "2") (pinfunction "2_2") (pintype "passive"))
      (node (ref "VD1") (pin "2") (pinfunction "К_2") (pintype "passive"))
    )
    (net (code "32") (name "Net-(VD2-К)") (class "Default")
      (node (ref "R1") (pin "1") (pinfunction "1_1") (pintype "passive"))
      (node (ref "R14") (pin "2") (pinfunction "2_2") (pintype "passive"))
      (node (ref "R18") (pin "2") (pinfunction "2_2") (pintype "passive"))
      (node (ref "VD2") (pin "2") (pinfunction "К_2") (pintype "passive"))
    )
    (net (code "33") (name "Net-(VD3-К)") (class "Default")
      (node (ref "R15") (pin "1") (pinfunction "1_1") (pintype "passive"))
      (node (ref "R19") (pin "2") (pinfunction "2_2") (pintype "passive"))
      (node (ref "R8") (pin "2") (pinfunction "2_2") (pintype "passive"))
      (node (ref "VD3") (pin "2") (pinfunction "К_2") (pintype "passive"))
    )
    (net (code "34") (name "Net-(VD4-К)") (class "Default")
      (node (ref "R16") (pin "2") (pinfunction "2_2") (pintype "passive"))
      (node (ref "R2") (pin "1") (pinfunction "1_1") (pintype "passive"))
      (node (ref "R20") (pin "2") (pinfunction "2_2") (pintype "passive"))
      (node (ref "VD4") (pin "2") (pinfunction "К_2") (pintype "passive"))
    )
    (net (code "35") (name "Net-(VT1-Б)") (class "Default")
      (node (ref "R4") (pin "2") (pinfunction "2_2") (pintype "passive"))
      (node (ref "R5") (pin "2") (pinfunction "2_2") (pintype "passive"))
      (node (ref "VT1") (pin "1") (pinfunction "Б_1") (pintype "passive"))
    )
    (net (code "36") (name "Net-(VT1-К)") (class "Default")
      (node (ref "R13") (pin "2") (pinfunction "2_2") (pintype "passive"))
      (node (ref "VT1") (pin "2") (pinfunction "К_2") (pintype "passive"))
    )
    (net (code "37") (name "Net-(VT2-Б)") (class "Default")
      (node (ref "R6") (pin "2") (pinfunction "2_2") (pintype "passive"))
      (node (ref "R7") (pin "2") (pinfunction "2_2") (pintype "passive"))
      (node (ref "VT2") (pin "1") (pinfunction "Б_1") (pintype "passive"))
    )
    (net (code "38") (name "Net-(VT2-К)") (class "Default")
      (node (ref "R14") (pin "1") (pinfunction "1_1") (pintype "passive"))
      (node (ref "VT2") (pin "2") (pinfunction "К_2") (pintype "passive"))
    )
    (net (code "39") (name "Net-(VT3-Б)") (class "Default")
      (node (ref "R10") (pin "2") (pinfunction "2_2") (pintype "passive"))
      (node (ref "R9") (pin "2") (pinfunction "2_2") (pintype "passive"))
      (node (ref "VT3") (pin "1") (pinfunction "Б_1") (pintype "passive"))
    )
    (net (code "40") (name "Net-(VT3-К)") (class "Default")
      (node (ref "R15") (pin "2") (pinfunction "2_2") (pintype "passive"))
      (node (ref "VT3") (pin "2") (pinfunction "К_2") (pintype "passive"))
    )
    (net (code "41") (name "Net-(VT4-Б)") (class "Default")
      (node (ref "R11") (pin "2") (pinfunction "2_2") (pintype "passive"))
      (node (ref "R12") (pin "2") (pinfunction "2_2") (pintype "passive"))
      (node (ref "VT4") (pin "1") (pinfunction "Б_1") (pintype "passive"))
    )
    (net (code "42") (name "Net-(VT4-К)") (class "Default")
      (node (ref "R16") (pin "1") (pinfunction "1_1") (pintype "passive"))
      (node (ref "VT4") (pin "2") (pinfunction "К_2") (pintype "passive"))
    )
    (net (code "43") (name "VCC") (class "Default")
      (node (ref "C10") (pin "1") (pinfunction "1_1") (pintype "passive"))
      (node (ref "C11") (pin "1") (pinfunction "1_1") (pintype "passive"))
      (node (ref "C4") (pin "2") (pinfunction "2_2") (pintype "passive"))
      (node (ref "C6") (pin "1") (pinfunction "1_1") (pintype "passive"))
      (node (ref "DA1") (pin "2") (pinfunction "Out_2") (pintype "passive"))
      (node (ref "DD1") (pin "1") (pinfunction "VBAT_1") (pintype "power_in"))
      (node (ref "DD1") (pin "24") (pinfunction "VDD_24") (pintype "power_in"))
      (node (ref "DD1") (pin "36") (pinfunction "VDD_36") (pintype "power_in"))
      (node (ref "DD1") (pin "48") (pinfunction "VDD_48") (pintype "power_in"))
      (node (ref "DD1") (pin "9") (pinfunction "VDDA_9") (pintype "power_in"))
      (node (ref "HL1") (pin "1") (pinfunction "А_1") (pintype "passive"))
      (node (ref "IC1") (pin "20") (pinfunction "VCC_20") (pintype "power_in"))
      (node (ref "XP9") (pin "1") (pintype "passive"))
    )
    (net (code "44") (name "unconnected-(DD1-PA4-Pad14)") (class "Default")
      (node (ref "DD1") (pin "14") (pinfunction "PA4_14") (pintype "bidirectional"))
    )
    (net (code "45") (name "unconnected-(DD1-PA5-Pad15)") (class "Default")
      (node (ref "DD1") (pin "15") (pinfunction "PA5_15") (pintype "bidirectional"))
    )
    (net (code "46") (name "unconnected-(DD1-PA6-Pad16)") (class "Default")
      (node (ref "DD1") (pin "16") (pinfunction "PA6_16") (pintype "bidirectional"))
    )
    (net (code "47") (name "unconnected-(DD1-PA7-Pad17)") (class "Default")
      (node (ref "DD1") (pin "17") (pinfunction "PA7_17") (pintype "bidirectional"))
    )
    (net (code "48") (name "unconnected-(DD1-PA12-Pad33)") (class "Default")
      (node (ref "DD1") (pin "33") (pinfunction "PA12_33") (pintype "bidirectional"))
    )
    (net (code "49") (name "unconnected-(DD1-PA15-Pad38)") (class "Default")
      (node (ref "DD1") (pin "38") (pinfunction "PA15_38") (pintype "bidirectional"))
    )
    (net (code "50") (name "unconnected-(DD1-PB0-Pad18)") (class "Default")
      (node (ref "DD1") (pin "18") (pinfunction "PB0_18") (pintype "bidirectional"))
    )
    (net (code "51") (name "unconnected-(DD1-PB1-Pad19)") (class "Default")
      (node (ref "DD1") (pin "19") (pinfunction "PB1_19") (pintype "bidirectional"))
    )
    (net (code "52") (name "unconnected-(DD1-PB7-Pad43)") (class "Default")
      (node (ref "DD1") (pin "43") (pinfunction "PB7_43") (pintype "bidirectional"))
    )
    (net (code "53") (name "unconnected-(DD1-PB12-Pad25)") (class "Default")
      (node (ref "DD1") (pin "25") (pinfunction "PB12_25") (pintype "bidirectional"))
    )
    (net (code "54") (name "unconnected-(DD1-PB13-Pad26)") (class "Default")
      (node (ref "DD1") (pin "26") (pinfunction "PB13_26") (pintype "bidirectional"))
    )
    (net (code "55") (name "unconnected-(DD1-PB14-Pad27)") (class "Default")
      (node (ref "DD1") (pin "27") (pinfunction "PB14_27") (pintype "bidirectional"))
    )
    (net (code "56") (name "unconnected-(DD1-PB15-Pad28)") (class "Default")
      (node (ref "DD1") (pin "28") (pinfunction "PB15_28") (pintype "bidirectional"))
    )
    (net (code "57") (name "unconnected-(DD1-PC13-TRTC-Pad2)") (class "Default")
      (node (ref "DD1") (pin "2") (pinfunction "PC13-TRTC_2") (pintype "bidirectional"))
    )
    (net (code "58") (name "unconnected-(DD1-PC14-OSC3I-Pad3)") (class "Default")
      (node (ref "DD1") (pin "3") (pinfunction "PC14-OSC3I_3") (pintype "bidirectional"))
    )
    (net (code "59") (name "unconnected-(DD1-PC15-OSC3O-Pad4)") (class "Default")
      (node (ref "DD1") (pin "4") (pinfunction "PC15-OSC3O_4") (pintype "bidirectional"))
    )
  )
)
